# dcp.net
KiCad netlist of a schematic drawn in EAGLE
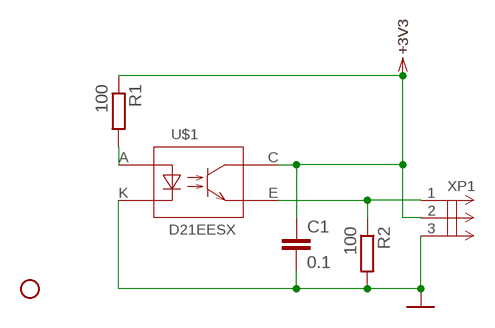
[diagram p0: schematic, sheet 1]

(export (version "E")
  (design (tool "Eeschema 10.0.6"))
  (components
    (comp (ref "C1")
      (value "0.1")
      (footprint "eagle-import:0805")
      (fields (field (name "PARTNO") "?"))
      (libsource (lib "eagle-import") (part "CAP0805"))
    )
    (comp (ref "JP1")
      (value "STAND-OFF-M3")
      (footprint "eagle-import:STAND-OFF-M3")
      (libsource (lib "eagle-import") (part "STAND-OFF-M3"))
    )
    (comp (ref "R1")
      (value "100")
      (footprint "eagle-import:0805")
      (libsource (lib "eagle-import") (part "RESISTOR0805"))
    )
    (comp (ref "R2")
      (value "100")
      (footprint "eagle-import:0805")
      (libsource (lib "eagle-import") (part "RESISTOR0805"))
    )
    (comp (ref "U$1")
      (value "D21EESX")
      (footprint "eagle-import:D21EESX")
      (libsource (lib "eagle-import") (part "D21EESX"))
    )
    (comp (ref "XP1")
      (value "PLD_1X03LONGPAD")
      (footprint "eagle-import:PLD_1X03_LONGPAD")
      (libsource (lib "eagle-import") (part "PLD_1X03LONGPAD"))
    )
  )
  (nets
    (net (code "1") (name "+3V3") (class "Default")
      (node (ref "C1") (pin "1") (pinfunction "1_1") (pintype "passive"))
      (node (ref "R1") (pin "1") (pinfunction "1_1") (pintype "passive"))
      (node (ref "U$1") (pin "C") (pinfunction "TC_C") (pintype "bidirectional"))
      (node (ref "XP1") (pin "2") (pinfunction "2_2") (pintype "passive"))
    )
    (net (code "2") (name "GND") (class "Default")
      (node (ref "C1") (pin "2") (pinfunction "2_2") (pintype "passive"))
      (node (ref "R2") (pin "2") (pinfunction "2_2") (pintype "passive"))
      (node (ref "U$1") (pin "K") (pinfunction "DC_K") (pintype "passive"))
      (node (ref "XP1") (pin "3") (pinfunction "3_3") (pintype "passive"))
    )
    (net (code "3") (name "Net-(U$1-DA)") (class "Default")
      (node (ref "R1") (pin "2") (pinfunction "2_2") (pintype "passive"))
      (node (ref "U$1") (pin "A") (pinfunction "DA_A") (pintype "passive"))
    )
    (net (code "4") (name "Net-(U$1-TE)") (class "Default")
      (node (ref "R2") (pin "1") (pinfunction "1_1") (pintype "passive"))
      (node (ref "U$1") (pin "E") (pinfunction "TE_E") (pintype "bidirectional"))
      (node (ref "XP1") (pin "1") (pinfunction "1_1") (pintype "passive"))
    )
  )
)
